# pcb1c.net
KiCad netlist of a schematic drawn in EAGLE
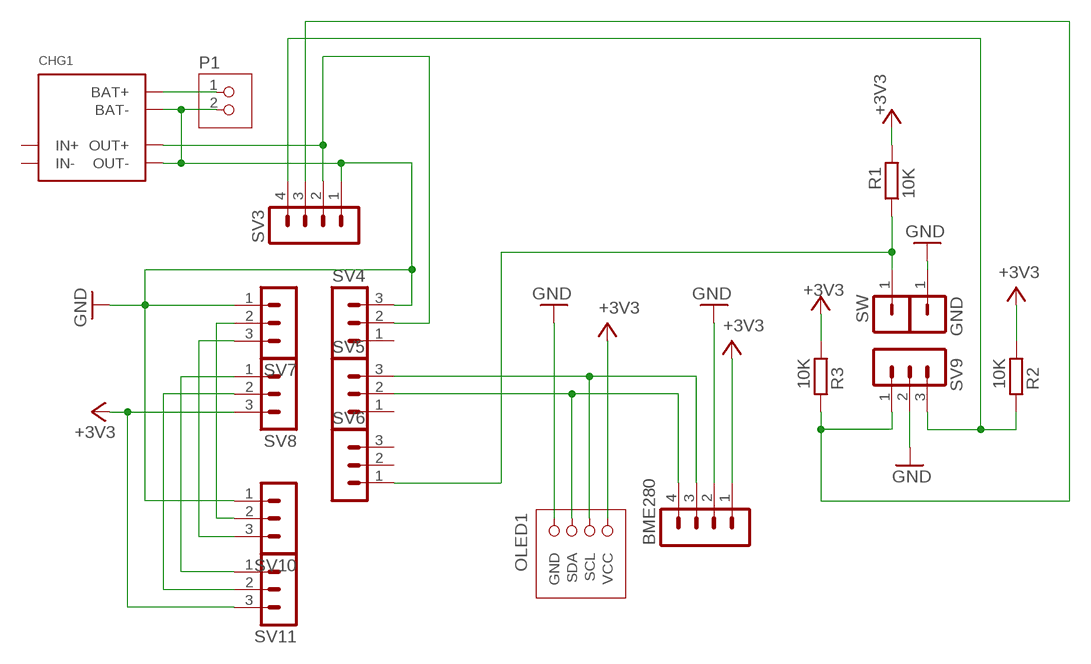
[diagram p0: schematic, sheet 1]

(export (version "E")
  (design (tool "Eeschema 10.0.6"))
  (components
    (comp (ref "BME280")
      (value "PINHEAD-MA04-1")
      (footprint "eagle-import:PINHEAD-MA04-1")
      (libsource (lib "eagle-import") (part "PINHEAD-MA04-1"))
    )
    (comp (ref "CHG1")
      (value "TP4056MOD2-TYPE-C")
      (footprint "eagle-import:TP4056MOD2-TYPE-C")
      (libsource (lib "eagle-import") (part "TP4056MOD2-TYPE-C"))
    )
    (comp (ref "GND")
      (value "PINHEAD-MA01-1")
      (footprint "eagle-import:PINHEAD-MA01-1")
      (libsource (lib "eagle-import") (part "PINHEAD-MA01-1"))
    )
    (comp (ref "OLED1")
      (value "OLED-SSD1306-0.96")
      (footprint "eagle-import:OLED-I2C-0.96")
      (libsource (lib "eagle-import") (part "OLED-SSD1306-0.96"))
    )
    (comp (ref "P1")
      (value "JST-PH2")
      (footprint "eagle-import:JST-PH2")
      (libsource (lib "eagle-import") (part "JST-PH2"))
    )
    (comp (ref "R1")
      (value "10K")
      (footprint "eagle-import:0204_5")
      (libsource (lib "eagle-import") (part "R-EU_0204/5"))
    )
    (comp (ref "R2")
      (value "10K")
      (footprint "eagle-import:0204_5")
      (libsource (lib "eagle-import") (part "R-EU_0204/5"))
    )
    (comp (ref "R3")
      (value "10K")
      (footprint "eagle-import:0204_5")
      (libsource (lib "eagle-import") (part "R-EU_0204/5"))
    )
    (comp (ref "SV3")
      (value "PINHEAD-MA04-1")
      (footprint "eagle-import:PINHEAD-MA04-1")
      (libsource (lib "eagle-import") (part "PINHEAD-MA04-1"))
    )
    (comp (ref "SV4")
      (value "PINHEAD-MA03-1")
      (footprint "eagle-import:PINHEAD-MA03-1")
      (libsource (lib "eagle-import") (part "PINHEAD-MA03-1"))
    )
    (comp (ref "SV5")
      (value "PINHEAD-MA03-1")
      (footprint "eagle-import:PINHEAD-MA03-1")
      (libsource (lib "eagle-import") (part "PINHEAD-MA03-1"))
    )
    (comp (ref "SV6")
      (value "PINHEAD-MA03-1")
      (footprint "eagle-import:PINHEAD-MA03-1")
      (libsource (lib "eagle-import") (part "PINHEAD-MA03-1"))
    )
    (comp (ref "SV7")
      (value "PINHEAD-MA03-1")
      (footprint "eagle-import:PINHEAD-MA03-1")
      (libsource (lib "eagle-import") (part "PINHEAD-MA03-1"))
    )
    (comp (ref "SV8")
      (value "PINHEAD-MA03-1")
      (footprint "eagle-import:PINHEAD-MA03-1")
      (libsource (lib "eagle-import") (part "PINHEAD-MA03-1"))
    )
    (comp (ref "SV9")
      (value "PINHEAD-MA03-1")
      (footprint "eagle-import:PINHEAD-MA03-1")
      (libsource (lib "eagle-import") (part "PINHEAD-MA03-1"))
    )
    (comp (ref "SV10")
      (value "PINHEAD-MA03-1")
      (footprint "eagle-import:PINHEAD-MA03-1")
      (libsource (lib "eagle-import") (part "PINHEAD-MA03-1"))
    )
    (comp (ref "SV11")
      (value "PINHEAD-MA03-1")
      (footprint "eagle-import:PINHEAD-MA03-1")
      (libsource (lib "eagle-import") (part "PINHEAD-MA03-1"))
    )
    (comp (ref "SW")
      (value "PINHEAD-MA01-1")
      (footprint "eagle-import:PINHEAD-MA01-1")
      (libsource (lib "eagle-import") (part "PINHEAD-MA01-1"))
    )
  )
  (nets
    (net (code "1") (name "+3V3") (class "Default")
      (node (ref "BME280") (pin "1") (pinfunction "1_1") (pintype "passive"))
      (node (ref "OLED1") (pin "VCC") (pinfunction "VCC_VCC") (pintype "bidirectional"))
      (node (ref "R1") (pin "2") (pinfunction "2_2") (pintype "passive"))
      (node (ref "R2") (pin "1") (pinfunction "1_1") (pintype "passive"))
      (node (ref "R3") (pin "1") (pinfunction "1_1") (pintype "passive"))
      (node (ref "SV11") (pin "3") (pinfunction "3_3") (pintype "passive"))
      (node (ref "SV8") (pin "3") (pinfunction "3_3") (pintype "passive"))
    )
    (net (code "2") (name "GND") (class "Default")
      (node (ref "BME280") (pin "2") (pinfunction "2_2") (pintype "passive"))
      (node (ref "CHG1") (pin "BAT-") (pinfunction "BAT-_BAT-") (pintype "passive"))
      (node (ref "CHG1") (pin "OUT-") (pinfunction "OUT-_OUT-") (pintype "passive"))
      (node (ref "GND") (pin "1") (pinfunction "1_1") (pintype "passive"))
      (node (ref "OLED1") (pin "GND") (pinfunction "GND_GND") (pintype "bidirectional"))
      (node (ref "P1") (pin "2") (pinfunction "2_2") (pintype "passive"))
      (node (ref "SV10") (pin "1") (pinfunction "1_1") (pintype "passive"))
      (node (ref "SV3") (pin "1") (pinfunction "1_1") (pintype "passive"))
      (node (ref "SV4") (pin "3") (pinfunction "3_3") (pintype "passive"))
      (node (ref "SV7") (pin "1") (pinfunction "1_1") (pintype "passive"))
      (node (ref "SV9") (pin "2") (pinfunction "2_2") (pintype "passive"))
    )
    (net (code "3") (name "Net-(BME280-Pad3)") (class "Default")
      (node (ref "BME280") (pin "3") (pinfunction "3_3") (pintype "passive"))
      (node (ref "OLED1") (pin "SCL") (pinfunction "SCL_SCL") (pintype "bidirectional"))
      (node (ref "SV5") (pin "3") (pinfunction "3_3") (pintype "passive"))
    )
    (net (code "4") (name "Net-(BME280-Pad4)") (class "Default")
      (node (ref "BME280") (pin "4") (pinfunction "4_4") (pintype "passive"))
      (node (ref "OLED1") (pin "SDA") (pinfunction "SDA_SDA") (pintype "bidirectional"))
      (node (ref "SV5") (pin "2") (pinfunction "2_2") (pintype "passive"))
    )
    (net (code "5") (name "Net-(CHG1-PadBAT+)") (class "Default")
      (node (ref "CHG1") (pin "BAT+") (pinfunction "BAT+_BAT+") (pintype "passive"))
      (node (ref "P1") (pin "1") (pinfunction "1_1") (pintype "passive"))
    )
    (net (code "6") (name "Net-(CHG1-PadOUT+)") (class "Default")
      (node (ref "CHG1") (pin "OUT+") (pinfunction "OUT+_OUT+") (pintype "passive"))
      (node (ref "SV3") (pin "2") (pinfunction "2_2") (pintype "passive"))
      (node (ref "SV4") (pin "2") (pinfunction "2_2") (pintype "passive"))
    )
    (net (code "7") (name "Net-(R1-Pad1)") (class "Default")
      (node (ref "R1") (pin "1") (pinfunction "1_1") (pintype "passive"))
      (node (ref "SV6") (pin "1") (pinfunction "1_1") (pintype "passive"))
      (node (ref "SW") (pin "1") (pinfunction "1_1") (pintype "passive"))
    )
    (net (code "8") (name "Net-(R2-Pad2)") (class "Default")
      (node (ref "R2") (pin "2") (pinfunction "2_2") (pintype "passive"))
      (node (ref "SV3") (pin "4") (pinfunction "4_4") (pintype "passive"))
      (node (ref "SV9") (pin "3") (pinfunction "3_3") (pintype "passive"))
    )
    (net (code "9") (name "Net-(R3-Pad2)") (class "Default")
      (node (ref "R3") (pin "2") (pinfunction "2_2") (pintype "passive"))
      (node (ref "SV3") (pin "3") (pinfunction "3_3") (pintype "passive"))
      (node (ref "SV9") (pin "1") (pinfunction "1_1") (pintype "passive"))
    )
    (net (code "10") (name "Net-(SV10-Pad2)") (class "Default")
      (node (ref "SV10") (pin "2") (pinfunction "2_2") (pintype "passive"))
      (node (ref "SV7") (pin "2") (pinfunction "2_2") (pintype "passive"))
    )
    (net (code "11") (name "Net-(SV10-Pad3)") (class "Default")
      (node (ref "SV10") (pin "3") (pinfunction "3_3") (pintype "passive"))
      (node (ref "SV7") (pin "3") (pinfunction "3_3") (pintype "passive"))
    )
    (net (code "12") (name "Net-(SV11-Pad1)") (class "Default")
      (node (ref "SV11") (pin "1") (pinfunction "1_1") (pintype "passive"))
      (node (ref "SV8") (pin "1") (pinfunction "1_1") (pintype "passive"))
    )
    (net (code "13") (name "Net-(SV11-Pad2)") (class "Default")
      (node (ref "SV11") (pin "2") (pinfunction "2_2") (pintype "passive"))
      (node (ref "SV8") (pin "2") (pinfunction "2_2") (pintype "passive"))
    )
    (net (code "14") (name "unconnected-(CHG1-PadIN+)") (class "Default")
      (node (ref "CHG1") (pin "IN+") (pinfunction "IN+_IN+") (pintype "passive"))
    )
    (net (code "15") (name "unconnected-(CHG1-PadIN-)") (class "Default")
      (node (ref "CHG1") (pin "IN-") (pinfunction "IN-_IN-") (pintype "passive"))
    )
    (net (code "16") (name "unconnected-(SV4-Pad1)") (class "Default")
      (node (ref "SV4") (pin "1") (pinfunction "1_1") (pintype "passive"))
    )
    (net (code "17") (name "unconnected-(SV5-Pad1)") (class "Default")
      (node (ref "SV5") (pin "1") (pinfunction "1_1") (pintype "passive"))
    )
    (net (code "18") (name "unconnected-(SV6-Pad2)") (class "Default")
      (node (ref "SV6") (pin "2") (pinfunction "2_2") (pintype "passive"))
    )
    (net (code "19") (name "unconnected-(SV6-Pad3)") (class "Default")
      (node (ref "SV6") (pin "3") (pinfunction "3_3") (pintype "passive"))
    )
  )
)
